# Reset_Pin.net
KiCad netlist of a schematic drawn in Altium Designer
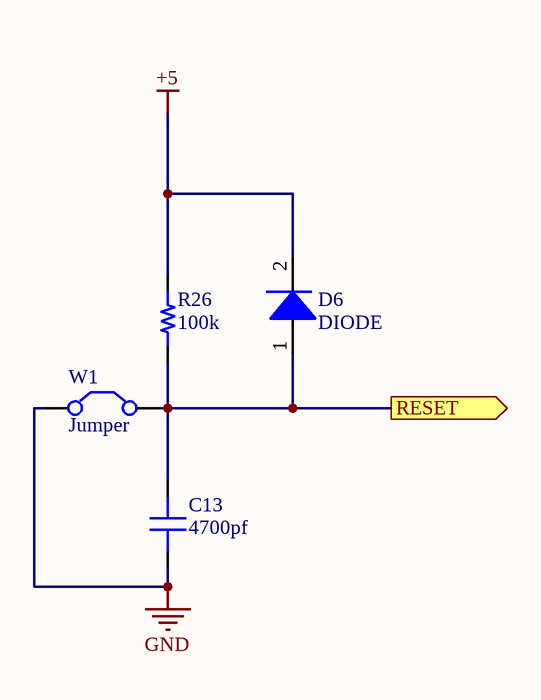
[diagram p0: Reset_Pin.SchDoc]

(export (version "E")
  (design (tool "Eeschema 10.0.6"))
  (components
    (comp (ref "C13")
      (value "4700pf")
      (footprint "CAP 0805/2012")
      (fields
        (field (name "Comment") "Capacitor MLCC 4700pf 25V CAP 0805/2012")
        (field (name "CREATED_BY") "Nick Mah")
      )
      (libsource (lib "Altium-Lib") (part "Capacitor"))
    )
    (comp (ref "D6")
      (value "DIODE")
      (footprint "SOD123F")
      (description "100V Reverse DC Voltage")
      (fields (field (name "MFRPARTNO") "1N4148W-7-F"))
      (libsource (lib "Altium-Lib") (part "DIODE"))
    )
    (comp (ref "R26")
      (value "100k")
      (footprint "RES 0805/2012")
      (fields
        (field (name "TOLERANCE") "1%")
        (field (name "POWER") "1/10W")
        (field (name "Comment") "Resistor 100k 0805 1/10W 1%")
        (field (name "CREATED_BY") "Nick Mah")
      )
      (libsource (lib "Altium-Lib") (part "Resistor"))
    )
    (comp (ref "W1")
      (value "Jumper")
      (footprint "XG8T-0231")
      (description "Jumper headers")
      (fields (field (name "MFRPARTNO") "XG8T-0231"))
      (libsource (lib "Altium-Lib") (part "Jumper"))
    )
  )
  (nets
    (net (code "1") (name "+5") (class "Default")
      (node (ref "D6") (pin "2") (pinfunction "K_2") (pintype "passive"))
      (node (ref "R26") (pin "2") (pinfunction "2_2") (pintype "passive"))
    )
    (net (code "2") (name "/RESET") (class "Default")
      (node (ref "C13") (pin "2") (pinfunction "2_2") (pintype "passive"))
      (node (ref "D6") (pin "1") (pinfunction "A_1") (pintype "passive"))
      (node (ref "R26") (pin "1") (pinfunction "1_1") (pintype "passive"))
      (node (ref "W1") (pin "2") (pinfunction "C2_2") (pintype "passive"))
    )
    (net (code "3") (name "GND") (class "Default")
      (node (ref "C13") (pin "1") (pinfunction "1_1") (pintype "passive"))
      (node (ref "W1") (pin "1") (pinfunction "C1_1") (pintype "passive"))
    )
  )
)
